# Counter_Display_v1_dynamicLED.net
KiCad netlist of a schematic drawn in Altium Designer
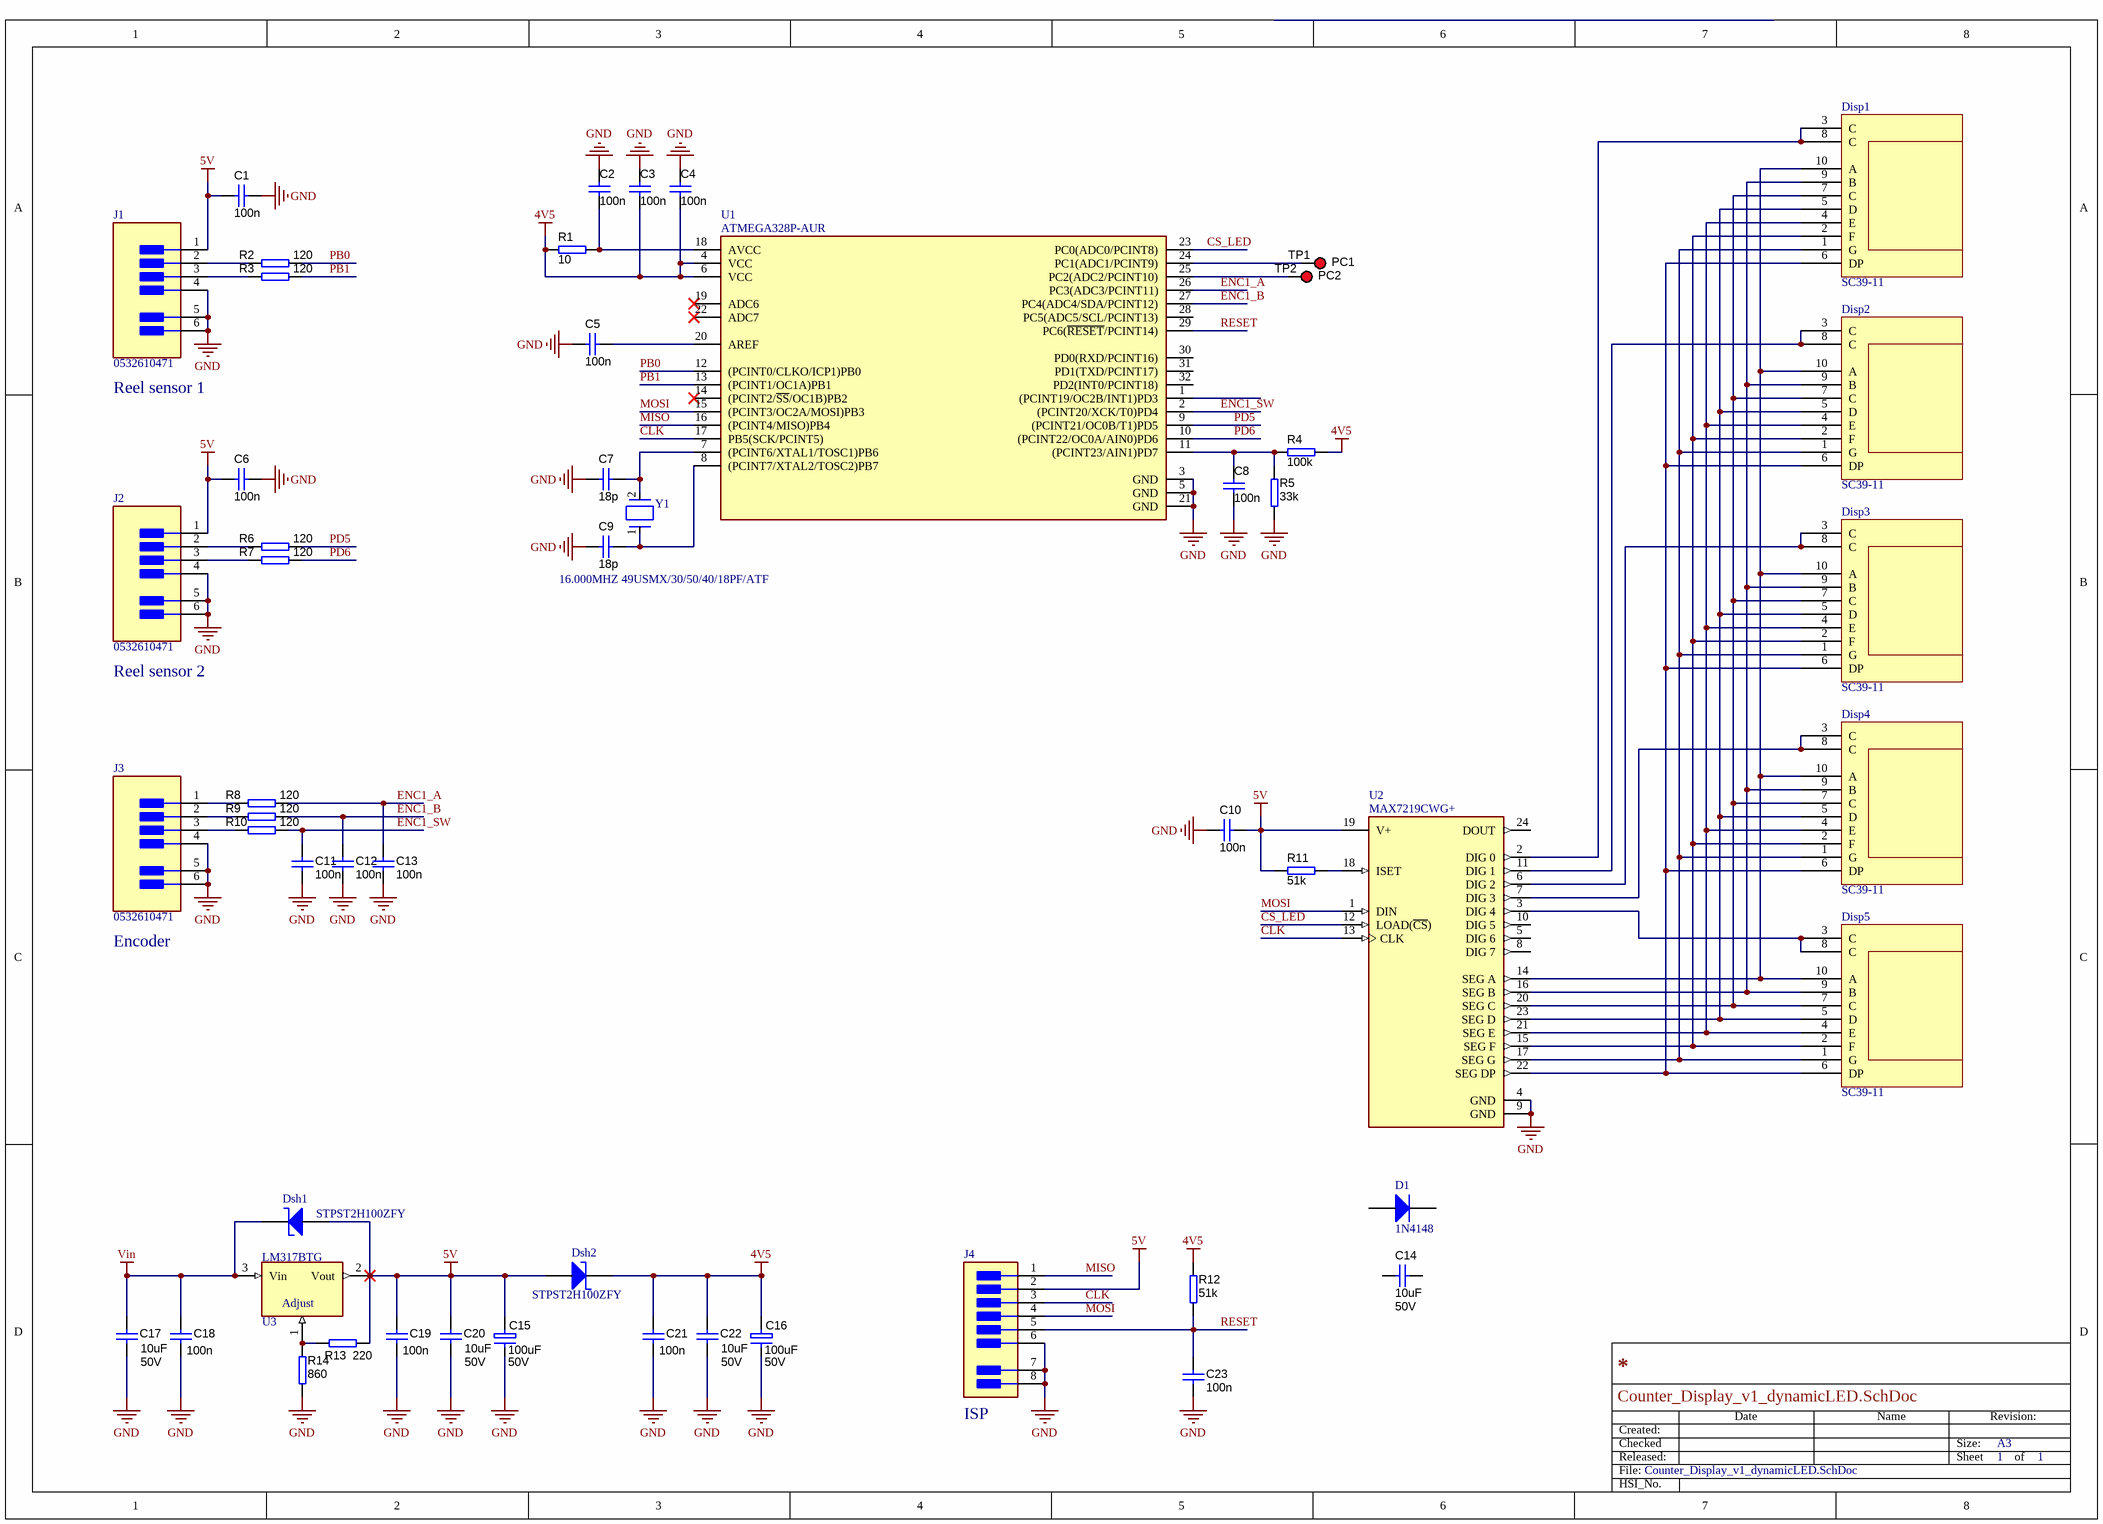
[diagram p0: Counter_Display_v1_dynamicLED.SchDoc]

(export (version "E")
  (design (tool "Eeschema 10.0.6"))
  (components
    (comp (ref "C1")
      (value "100n")
      (footprint "0805_HV")
      (description "CAP, CERM, +/- 10%, X7S,  0805")
      (libsource (lib "Const_Cur_Source") (part "C0805"))
    )
    (comp (ref "C2")
      (value "100n")
      (footprint "0805_HV")
      (description "CAP, CERM, +/- 10%, X7S,  0805")
      (libsource (lib "Const_Cur_Source") (part "C0805"))
    )
    (comp (ref "C3")
      (value "100n")
      (footprint "0805_HV")
      (description "CAP, CERM, +/- 10%, X7S,  0805")
      (libsource (lib "Const_Cur_Source") (part "C0805"))
    )
    (comp (ref "C4")
      (value "100n")
      (footprint "0805_HV")
      (description "CAP, CERM, +/- 10%, X7S,  0805")
      (libsource (lib "Const_Cur_Source") (part "C0805"))
    )
    (comp (ref "C5")
      (value "100n")
      (footprint "0805_HV")
      (description "CAP, CERM, +/- 10%, X7S,  0805")
      (libsource (lib "Const_Cur_Source") (part "C0805"))
    )
    (comp (ref "C6")
      (value "100n")
      (footprint "0805_HV")
      (description "CAP, CERM, +/- 10%, X7S,  0805")
      (libsource (lib "Const_Cur_Source") (part "C0805"))
    )
    (comp (ref "C7")
      (value "18p")
      (footprint "0805_HV")
      (description "CAP, CERM, +/- 10%, X7S,  0805")
      (libsource (lib "Const_Cur_Source") (part "C0805"))
    )
    (comp (ref "C8")
      (value "100n")
      (footprint "0805_HV")
      (description "CAP, CERM, +/- 10%, X7S,  0805")
      (libsource (lib "Const_Cur_Source") (part "C0805"))
    )
    (comp (ref "C9")
      (value "18p")
      (footprint "0805_HV")
      (description "CAP, CERM, +/- 10%, X7S,  0805")
      (libsource (lib "Const_Cur_Source") (part "C0805"))
    )
    (comp (ref "C10")
      (value "100n")
      (footprint "0805_HV")
      (description "CAP, CERM, +/- 10%, X7S,  0805")
      (libsource (lib "Const_Cur_Source") (part "C0805"))
    )
    (comp (ref "C11")
      (value "100n")
      (footprint "0805_HV")
      (description "CAP, CERM, +/- 10%, X7S,  0805")
      (libsource (lib "Const_Cur_Source") (part "C0805"))
    )
    (comp (ref "C12")
      (value "100n")
      (footprint "0805_HV")
      (description "CAP, CERM, +/- 10%, X7S,  0805")
      (libsource (lib "Const_Cur_Source") (part "C0805"))
    )
    (comp (ref "C13")
      (value "100n")
      (footprint "0805_HV")
      (description "CAP, CERM, +/- 10%, X7S,  0805")
      (libsource (lib "Const_Cur_Source") (part "C0805"))
    )
    (comp (ref "C14")
      (value "10uF")
      (footprint "1206_180")
      (description "CAP, CERM, NP0, 1206")
      (fields (field (name "VALUE1") "50V"))
      (libsource (lib "Const_Cur_Source") (part "C1206"))
    )
    (comp (ref "C15")
      (value "100uF")
      (footprint "Elco_Flat_v1")
      (description "CAP, Elco")
      (fields (field (name "VALUE1") "50V"))
      (libsource (lib "Const_Cur_Source") (part "C_Elco"))
    )
    (comp (ref "C16")
      (value "100uF")
      (footprint "Elco_Flat_v1")
      (description "CAP, Elco")
      (fields (field (name "VALUE1") "50V"))
      (libsource (lib "Const_Cur_Source") (part "C_Elco"))
    )
    (comp (ref "C17")
      (value "10uF")
      (footprint "1206_180")
      (description "CAP, CERM, NP0, 1206")
      (fields (field (name "VALUE1") "50V"))
      (libsource (lib "Const_Cur_Source") (part "C1206"))
    )
    (comp (ref "C18")
      (value "100n")
      (footprint "1206")
      (description "CAP, CERM, +/- 10%, X7S,  0805")
      (libsource (lib "Const_Cur_Source") (part "C0805"))
    )
    (comp (ref "C19")
      (value "100n")
      (footprint "0805_HV")
      (description "CAP, CERM, +/- 10%, X7S,  0805")
      (libsource (lib "Const_Cur_Source") (part "C0805"))
    )
    (comp (ref "C20")
      (value "10uF")
      (footprint "1206_180")
      (description "CAP, CERM, NP0, 1206")
      (fields (field (name "VALUE1") "50V"))
      (libsource (lib "Const_Cur_Source") (part "C1206"))
    )
    (comp (ref "C21")
      (value "100n")
      (footprint "0805_HV")
      (description "CAP, CERM, +/- 10%, X7S,  0805")
      (libsource (lib "Const_Cur_Source") (part "C0805"))
    )
    (comp (ref "C22")
      (value "10uF")
      (footprint "1206_180")
      (description "CAP, CERM, NP0, 1206")
      (fields (field (name "VALUE1") "50V"))
      (libsource (lib "Const_Cur_Source") (part "C1206"))
    )
    (comp (ref "C23")
      (value "100n")
      (footprint "0805_HV")
      (description "CAP, CERM, +/- 10%, X7S,  0805")
      (libsource (lib "Const_Cur_Source") (part "C0805"))
    )
    (comp (ref "D1")
      (value "1N4148")
      (footprint "1N4148 (1005)")
      (description "Diode")
      (fields (field (name "Comment") "DIODE_MINI_MELF"))
      (libsource (lib "Const_Cur_Source") (part "DIODE_MINI_MELF"))
    )
    (comp (ref "Disp1")
      (value "SC39-11")
      (footprint "7-Segment-LED  (SC39-11G)")
      (description "SC 39-11 GN")
      (libsource (lib "Const_Cur_Source") (part "SC39-11"))
    )
    (comp (ref "Disp2")
      (value "SC39-11")
      (footprint "7-Segment-LED  (SC39-11G)")
      (description "SC 39-11 GN")
      (libsource (lib "Const_Cur_Source") (part "SC39-11"))
    )
    (comp (ref "Disp3")
      (value "SC39-11")
      (footprint "7-Segment-LED  (SC39-11G)")
      (description "SC 39-11 GN")
      (libsource (lib "Const_Cur_Source") (part "SC39-11"))
    )
    (comp (ref "Disp4")
      (value "SC39-11")
      (footprint "7-Segment-LED  (SC39-11G)")
      (description "SC 39-11 GN")
      (libsource (lib "Const_Cur_Source") (part "SC39-11"))
    )
    (comp (ref "Disp5")
      (value "SC39-11")
      (footprint "7-Segment-LED  (SC39-11G)")
      (description "SC 39-11 GN")
      (libsource (lib "Const_Cur_Source") (part "SC39-11"))
    )
    (comp (ref "Dsh1")
      (value "STPST2H100ZFY")
      (footprint "ONSC-SOD-123-2-425-04_V")
      (description "Diode Shottky")
      (fields (field (name "Comment") "DIODE_Shottky"))
      (libsource (lib "Const_Cur_Source") (part "DIODE_Shottky"))
    )
    (comp (ref "Dsh2")
      (value "STPST2H100ZFY")
      (footprint "ONSC-SOD-123-2-425-04_V")
      (description "Diode Shottky")
      (fields (field (name "Comment") "DIODE_Shottky"))
      (libsource (lib "Const_Cur_Source") (part "DIODE_Shottky"))
    )
    (comp (ref "J1")
      (value "0532610471")
      (footprint "Molex_0532610471_0")
      (libsource (lib "Const_Cur_Source") (part "0532610471"))
    )
    (comp (ref "J2")
      (value "0532610471")
      (footprint "Molex_0532610471_0")
      (libsource (lib "Const_Cur_Source") (part "0532610471"))
    )
    (comp (ref "J3")
      (value "0532610471")
      (footprint "Molex_0532610471_0")
      (libsource (lib "Const_Cur_Source") (part "0532610471"))
    )
    (comp (ref "J4")
      (value "53261-0671")
      (footprint "Molex_53261-0671_0")
      (libsource (lib "Const_Cur_Source") (part "53261-0671"))
    )
    (comp (ref "R1")
      (value "10")
      (footprint "0805_HV")
      (description "RES, 1%, 0.1 W, 0805")
      (libsource (lib "Const_Cur_Source") (part "R0805"))
    )
    (comp (ref "R2")
      (value "120")
      (footprint "0805_HV")
      (description "RES, 1%, 0.1 W, 0805")
      (libsource (lib "Const_Cur_Source") (part "R0805"))
    )
    (comp (ref "R3")
      (value "120")
      (footprint "0805_HV")
      (description "RES, 1%, 0.1 W, 0805")
      (libsource (lib "Const_Cur_Source") (part "R0805"))
    )
    (comp (ref "R4")
      (value "100k")
      (footprint "0805_HV")
      (description "RES, 1%, 0.1 W, 0805")
      (libsource (lib "Const_Cur_Source") (part "R0805"))
    )
    (comp (ref "R5")
      (value "33k")
      (footprint "0805_HV")
      (description "RES, 1%, 0.1 W, 0805")
      (libsource (lib "Const_Cur_Source") (part "R0805"))
    )
    (comp (ref "R6")
      (value "120")
      (footprint "0805_HV")
      (description "RES, 1%, 0.1 W, 0805")
      (libsource (lib "Const_Cur_Source") (part "R0805"))
    )
    (comp (ref "R7")
      (value "120")
      (footprint "0805_HV")
      (description "RES, 1%, 0.1 W, 0805")
      (libsource (lib "Const_Cur_Source") (part "R0805"))
    )
    (comp (ref "R8")
      (value "120")
      (footprint "0805_HV")
      (description "RES, 1%, 0.1 W, 0805")
      (libsource (lib "Const_Cur_Source") (part "R0805"))
    )
    (comp (ref "R9")
      (value "120")
      (footprint "0805_HV")
      (description "RES, 1%, 0.1 W, 0805")
      (libsource (lib "Const_Cur_Source") (part "R0805"))
    )
    (comp (ref "R10")
      (value "120")
      (footprint "0805_HV")
      (description "RES, 1%, 0.1 W, 0805")
      (libsource (lib "Const_Cur_Source") (part "R0805"))
    )
    (comp (ref "R11")
      (value "51k")
      (footprint "0805_HV")
      (description "RES, 1%, 0.1 W, 0805")
      (libsource (lib "Const_Cur_Source") (part "R0805"))
    )
    (comp (ref "R12")
      (value "51k")
      (footprint "0805_HV")
      (description "RES, 1%, 0.1 W, 0805")
      (libsource (lib "Const_Cur_Source") (part "R0805"))
    )
    (comp (ref "R13")
      (value "220")
      (footprint "0805_HV")
      (description "RES, 1%, 0.1 W, 0805")
      (libsource (lib "Const_Cur_Source") (part "R0805"))
    )
    (comp (ref "R14")
      (value "860")
      (footprint "0805_HV")
      (description "RES, 1%, 0.1 W, 0805")
      (libsource (lib "Const_Cur_Source") (part "R0805"))
    )
    (comp (ref "TP1")
      (value "PC1")
      (footprint "TP")
      (description "Test Point, Miniature, Red, TH")
      (fields
        (field (name "PARTNUMBER") "5000")
        (field (name "MANUFACTURER") "Keystone")
        (field (name "PUBLISHER") "Texas Instruments")
      )
      (libsource (lib "Const_Cur_Source") (part "TP"))
    )
    (comp (ref "TP2")
      (value "PC2")
      (footprint "TP")
      (description "Test Point, Miniature, Red, TH")
      (fields
        (field (name "PARTNUMBER") "5000")
        (field (name "MANUFACTURER") "Keystone")
        (field (name "PUBLISHER") "Texas Instruments")
      )
      (libsource (lib "Const_Cur_Source") (part "TP"))
    )
    (comp (ref "U1")
      (value "ATMEGA328P-AU")
      (footprint "ATMEGA328P-AU_0")
      (description "IC AVR AVR® ATmega Microcontroller IC 8-Bit 20MHz 32KB (16K x 16) FLASH 32-TQFP (7x7)")
      (fields
        (field (name "MANUFACTURER") "Atmel")
        (field (name "MOUSER PART NUMBER") "556-ATMEGA328P-AUR")
        (field (name "PART NUMBER") "ATMEGA328P-AUR")
      )
      (libsource (lib "Const_Cur_Source") (part "ATMEGA328P-AU"))
    )
    (comp (ref "U2")
      (value "MAX7219CWG+")
      (footprint "Maxim_Integrated_W24-1_IPC_A")
      (libsource (lib "Const_Cur_Source") (part "MAX7219CWG+"))
    )
    (comp (ref "U3")
      (value "LM317BTG")
      (footprint "ON_Semi_221AB-01_0")
      (libsource (lib "Const_Cur_Source") (part "LM317BTG"))
    )
    (comp (ref "Y1")
      (value "Qartz_16.000MHZ_49USMX-30-50-40-18PF-ATF_eec")
      (footprint "Quartz_16.000MHZ_49USMX-30-50-40-18PF-ATF_0")
      (description "CRYS")
      (fields
        (field (name "MANUFACTURER") "Euroquartz")
        (field (name "OCTOPART PART NUMBER") "45978c55d5b29a50")
        (field (name "PART NUMBER") "16.000MHZ 49USMX/30/50/40/18PF/ATF")
      )
      (libsource (lib "Const_Cur_Source") (part "Qartz_16.000MHZ_49USMX-30-50-40-18PF-ATF_eec"))
    )
  )
  (nets
    (net (code "1") (name "/CLK") (class "Default")
      (node (ref "J4") (pin "3") (pinfunction "3_3") (pintype "passive"))
      (node (ref "U1") (pin "17") (pinfunction "PB5(SCK/PCINT5)_17") (pintype "passive"))
      (node (ref "U2") (pin "13") (pinfunction "CLK_13") (pintype "input"))
    )
    (net (code "2") (name "/CS_LED") (class "Default")
      (node (ref "U1") (pin "23") (pinfunction "PC0(ADC0/PCINT8)_23") (pintype "passive"))
      (node (ref "U2") (pin "12") (pinfunction "LOAD(~{CS})_12") (pintype "input"))
    )
    (net (code "3") (name "/ENC1_A") (class "Default")
      (node (ref "C13") (pin "2") (pinfunction "2_2") (pintype "passive"))
      (node (ref "R8") (pin "2") (pinfunction "2_2") (pintype "passive"))
      (node (ref "U1") (pin "26") (pinfunction "PC3(ADC3/PCINT11)_26") (pintype "passive"))
    )
    (net (code "4") (name "/ENC1_B") (class "Default")
      (node (ref "C12") (pin "2") (pinfunction "2_2") (pintype "passive"))
      (node (ref "R9") (pin "2") (pinfunction "2_2") (pintype "passive"))
      (node (ref "U1") (pin "27") (pinfunction "PC4(ADC4/SDA/PCINT12)_27") (pintype "passive"))
    )
    (net (code "5") (name "/ENC1_SW") (class "Default")
      (node (ref "C11") (pin "2") (pinfunction "2_2") (pintype "passive"))
      (node (ref "R10") (pin "2") (pinfunction "2_2") (pintype "passive"))
      (node (ref "U1") (pin "2") (pinfunction "(PCINT20/XCK/T0)PD4_2") (pintype "passive"))
    )
    (net (code "6") (name "/MISO") (class "Default")
      (node (ref "J4") (pin "1") (pinfunction "1_1") (pintype "passive"))
      (node (ref "U1") (pin "16") (pinfunction "(PCINT4/MISO)PB4_16") (pintype "passive"))
    )
    (net (code "7") (name "/MOSI") (class "Default")
      (node (ref "J4") (pin "4") (pinfunction "4_4") (pintype "passive"))
      (node (ref "U1") (pin "15") (pinfunction "(PCINT3/OC2A/MOSI)PB3_15") (pintype "passive"))
      (node (ref "U2") (pin "1") (pinfunction "DIN_1") (pintype "input"))
    )
    (net (code "8") (name "/PB0") (class "Default")
      (node (ref "R2") (pin "2") (pinfunction "2_2") (pintype "passive"))
      (node (ref "U1") (pin "12") (pinfunction "(PCINT0/CLKO/ICP1)PB0_12") (pintype "passive"))
    )
    (net (code "9") (name "/PB1") (class "Default")
      (node (ref "R3") (pin "2") (pinfunction "2_2") (pintype "passive"))
      (node (ref "U1") (pin "13") (pinfunction "(PCINT1/OC1A)PB1_13") (pintype "passive"))
    )
    (net (code "10") (name "/PD5") (class "Default")
      (node (ref "R6") (pin "2") (pinfunction "2_2") (pintype "passive"))
      (node (ref "U1") (pin "9") (pinfunction "(PCINT21/OC0B/T1)PD5_9") (pintype "passive"))
    )
    (net (code "11") (name "/PD6") (class "Default")
      (node (ref "R7") (pin "2") (pinfunction "2_2") (pintype "passive"))
      (node (ref "U1") (pin "10") (pinfunction "(PCINT22/OC0A/AIN0)PD6_10") (pintype "passive"))
    )
    (net (code "12") (name "/RESET") (class "Default")
      (node (ref "C23") (pin "2") (pinfunction "2_2") (pintype "passive"))
      (node (ref "J4") (pin "5") (pinfunction "5_5") (pintype "passive"))
      (node (ref "R12") (pin "1") (pinfunction "1_1") (pintype "passive"))
      (node (ref "U1") (pin "29") (pinfunction "PC6(~{RESET}/PCINT14)_29") (pintype "passive"))
    )
    (net (code "13") (name "4V5") (class "Default")
      (node (ref "C16") (pin "1") (pinfunction "1_1") (pintype "passive"))
      (node (ref "C21") (pin "1") (pinfunction "1_1") (pintype "passive"))
      (node (ref "C22") (pin "1") (pinfunction "1_1") (pintype "passive"))
      (node (ref "C3") (pin "1") (pinfunction "1_1") (pintype "passive"))
      (node (ref "C4") (pin "1") (pinfunction "1_1") (pintype "passive"))
      (node (ref "Dsh2") (pin "K") (pinfunction "K_K") (pintype "passive"))
      (node (ref "R1") (pin "1") (pinfunction "1_1") (pintype "passive"))
      (node (ref "R12") (pin "2") (pinfunction "2_2") (pintype "passive"))
      (node (ref "R4") (pin "2") (pinfunction "2_2") (pintype "passive"))
      (node (ref "U1") (pin "4") (pinfunction "VCC_4") (pintype "passive"))
      (node (ref "U1") (pin "6") (pinfunction "VCC_6") (pintype "passive"))
    )
    (net (code "14") (name "5V") (class "Default")
      (node (ref "C1") (pin "1") (pinfunction "1_1") (pintype "passive"))
      (node (ref "C10") (pin "2") (pinfunction "2_2") (pintype "passive"))
      (node (ref "C15") (pin "1") (pinfunction "1_1") (pintype "passive"))
      (node (ref "C19") (pin "1") (pinfunction "1_1") (pintype "passive"))
      (node (ref "C20") (pin "1") (pinfunction "1_1") (pintype "passive"))
      (node (ref "C6") (pin "1") (pinfunction "1_1") (pintype "passive"))
      (node (ref "Dsh1") (pin "A") (pinfunction "A_A") (pintype "passive"))
      (node (ref "Dsh2") (pin "A") (pinfunction "A_A") (pintype "passive"))
      (node (ref "J1") (pin "1") (pinfunction "1_1") (pintype "passive"))
      (node (ref "J2") (pin "1") (pinfunction "1_1") (pintype "passive"))
      (node (ref "J4") (pin "2") (pinfunction "2_2") (pintype "passive"))
      (node (ref "R11") (pin "1") (pinfunction "1_1") (pintype "passive"))
      (node (ref "R13") (pin "1") (pinfunction "1_1") (pintype "passive"))
      (node (ref "U2") (pin "19") (pinfunction "V+_19") (pintype "power_in"))
      (node (ref "U3") (pin "2") (pinfunction "Vout_2") (pintype "output"))
    )
    (net (code "15") (name "GND") (class "Default")
      (node (ref "C1") (pin "2") (pinfunction "2_2") (pintype "passive"))
      (node (ref "C10") (pin "1") (pinfunction "1_1") (pintype "passive"))
      (node (ref "C11") (pin "1") (pinfunction "1_1") (pintype "passive"))
      (node (ref "C12") (pin "1") (pinfunction "1_1") (pintype "passive"))
      (node (ref "C13") (pin "1") (pinfunction "1_1") (pintype "passive"))
      (node (ref "C15") (pin "2") (pinfunction "2_2") (pintype "passive"))
      (node (ref "C16") (pin "2") (pinfunction "2_2") (pintype "passive"))
      (node (ref "C17") (pin "2") (pinfunction "2_2") (pintype "passive"))
      (node (ref "C18") (pin "2") (pinfunction "2_2") (pintype "passive"))
      (node (ref "C19") (pin "2") (pinfunction "2_2") (pintype "passive"))
      (node (ref "C2") (pin "2") (pinfunction "2_2") (pintype "passive"))
      (node (ref "C20") (pin "2") (pinfunction "2_2") (pintype "passive"))
      (node (ref "C21") (pin "2") (pinfunction "2_2") (pintype "passive"))
      (node (ref "C22") (pin "2") (pinfunction "2_2") (pintype "passive"))
      (node (ref "C23") (pin "1") (pinfunction "1_1") (pintype "passive"))
      (node (ref "C3") (pin "2") (pinfunction "2_2") (pintype "passive"))
      (node (ref "C4") (pin "2") (pinfunction "2_2") (pintype "passive"))
      (node (ref "C5") (pin "2") (pinfunction "2_2") (pintype "passive"))
      (node (ref "C6") (pin "2") (pinfunction "2_2") (pintype "passive"))
      (node (ref "C7") (pin "2") (pinfunction "2_2") (pintype "passive"))
      (node (ref "C8") (pin "1") (pinfunction "1_1") (pintype "passive"))
      (node (ref "C9") (pin "2") (pinfunction "2_2") (pintype "passive"))
      (node (ref "J1") (pin "4") (pinfunction "4_4") (pintype "passive"))
      (node (ref "J1") (pin "5") (pinfunction "MNT_1_5") (pintype "passive"))
      (node (ref "J1") (pin "6") (pinfunction "MNT_2_6") (pintype "passive"))
      (node (ref "J2") (pin "4") (pinfunction "4_4") (pintype "passive"))
      (node (ref "J2") (pin "5") (pinfunction "MNT_1_5") (pintype "passive"))
      (node (ref "J2") (pin "6") (pinfunction "MNT_2_6") (pintype "passive"))
      (node (ref "J3") (pin "4") (pinfunction "4_4") (pintype "passive"))
      (node (ref "J3") (pin "5") (pinfunction "MNT_1_5") (pintype "passive"))
      (node (ref "J3") (pin "6") (pinfunction "MNT_2_6") (pintype "passive"))
      (node (ref "J4") (pin "6") (pinfunction "6_6") (pintype "passive"))
      (node (ref "J4") (pin "7") (pinfunction "MNT_1_7") (pintype "passive"))
      (node (ref "J4") (pin "8") (pinfunction "MNT_2_8") (pintype "passive"))
      (node (ref "R14") (pin "2") (pinfunction "2_2") (pintype "passive"))
      (node (ref "R5") (pin "1") (pinfunction "1_1") (pintype "passive"))
      (node (ref "U1") (pin "21") (pinfunction "GND_21") (pintype "passive"))
      (node (ref "U1") (pin "3") (pinfunction "GND_3") (pintype "passive"))
      (node (ref "U1") (pin "5") (pinfunction "GND_5") (pintype "passive"))
      (node (ref "U2") (pin "4") (pinfunction "GND_4") (pintype "power_in"))
      (node (ref "U2") (pin "9") (pinfunction "GND_9") (pintype "power_in"))
    )
    (net (code "16") (name "Net-(Disp1-A)") (class "Default")
      (node (ref "Disp1") (pin "10") (pinfunction "A_10") (pintype "passive"))
      (node (ref "Disp2") (pin "10") (pinfunction "A_10") (pintype "passive"))
      (node (ref "Disp3") (pin "10") (pinfunction "A_10") (pintype "passive"))
      (node (ref "Disp4") (pin "10") (pinfunction "A_10") (pintype "passive"))
      (node (ref "Disp5") (pin "10") (pinfunction "A_10") (pintype "passive"))
      (node (ref "U2") (pin "14") (pinfunction "SEG_A_14") (pintype "output"))
    )
    (net (code "17") (name "Net-(Disp1-B)") (class "Default")
      (node (ref "Disp1") (pin "9") (pinfunction "B_9") (pintype "passive"))
      (node (ref "Disp2") (pin "9") (pinfunction "B_9") (pintype "passive"))
      (node (ref "Disp3") (pin "9") (pinfunction "B_9") (pintype "passive"))
      (node (ref "Disp4") (pin "9") (pinfunction "B_9") (pintype "passive"))
      (node (ref "Disp5") (pin "9") (pinfunction "B_9") (pintype "passive"))
      (node (ref "U2") (pin "16") (pinfunction "SEG_B_16") (pintype "output"))
    )
    (net (code "18") (name "Net-(Disp1-D)") (class "Default")
      (node (ref "Disp1") (pin "5") (pinfunction "D_5") (pintype "passive"))
      (node (ref "Disp2") (pin "5") (pinfunction "D_5") (pintype "passive"))
      (node (ref "Disp3") (pin "5") (pinfunction "D_5") (pintype "passive"))
      (node (ref "Disp4") (pin "5") (pinfunction "D_5") (pintype "passive"))
      (node (ref "Disp5") (pin "5") (pinfunction "D_5") (pintype "passive"))
      (node (ref "U2") (pin "23") (pinfunction "SEG_D_23") (pintype "output"))
    )
    (net (code "19") (name "Net-(Disp1-DP)") (class "Default")
      (node (ref "Disp1") (pin "6") (pinfunction "DP_6") (pintype "passive"))
      (node (ref "Disp2") (pin "6") (pinfunction "DP_6") (pintype "passive"))
      (node (ref "Disp3") (pin "6") (pinfunction "DP_6") (pintype "passive"))
      (node (ref "Disp4") (pin "6") (pinfunction "DP_6") (pintype "passive"))
      (node (ref "Disp5") (pin "6") (pinfunction "DP_6") (pintype "passive"))
      (node (ref "U2") (pin "22") (pinfunction "SEG_DP_22") (pintype "output"))
    )
    (net (code "20") (name "Net-(Disp1-E)") (class "Default")
      (node (ref "Disp1") (pin "4") (pinfunction "E_4") (pintype "passive"))
      (node (ref "Disp2") (pin "4") (pinfunction "E_4") (pintype "passive"))
      (node (ref "Disp3") (pin "4") (pinfunction "E_4") (pintype "passive"))
      (node (ref "Disp4") (pin "4") (pinfunction "E_4") (pintype "passive"))
      (node (ref "Disp5") (pin "4") (pinfunction "E_4") (pintype "passive"))
      (node (ref "U2") (pin "21") (pinfunction "SEG_E_21") (pintype "output"))
    )
    (net (code "21") (name "Net-(Disp1-F)") (class "Default")
      (node (ref "Disp1") (pin "2") (pinfunction "F_2") (pintype "passive"))
      (node (ref "Disp2") (pin "2") (pinfunction "F_2") (pintype "passive"))
      (node (ref "Disp3") (pin "2") (pinfunction "F_2") (pintype "passive"))
      (node (ref "Disp4") (pin "2") (pinfunction "F_2") (pintype "passive"))
      (node (ref "Disp5") (pin "2") (pinfunction "F_2") (pintype "passive"))
      (node (ref "U2") (pin "15") (pinfunction "SEG_F_15") (pintype "output"))
    )
    (net (code "22") (name "Net-(Disp1-G)") (class "Default")
      (node (ref "Disp1") (pin "1") (pinfunction "G_1") (pintype "passive"))
      (node (ref "Disp2") (pin "1") (pinfunction "G_1") (pintype "passive"))
      (node (ref "Disp3") (pin "1") (pinfunction "G_1") (pintype "passive"))
      (node (ref "Disp4") (pin "1") (pinfunction "G_1") (pintype "passive"))
      (node (ref "Disp5") (pin "1") (pinfunction "G_1") (pintype "passive"))
      (node (ref "U2") (pin "17") (pinfunction "SEG_G_17") (pintype "output"))
    )
    (net (code "23") (name "Net-(J1-Pad2)") (class "Default")
      (node (ref "J1") (pin "2") (pinfunction "2_2") (pintype "passive"))
      (node (ref "R2") (pin "1") (pinfunction "1_1") (pintype "passive"))
    )
    (net (code "24") (name "Net-(J1-Pad3)") (class "Default")
      (node (ref "J1") (pin "3") (pinfunction "3_3") (pintype "passive"))
      (node (ref "R3") (pin "1") (pinfunction "1_1") (pintype "passive"))
    )
    (net (code "25") (name "Net-(J2-Pad2)") (class "Default")
      (node (ref "J2") (pin "2") (pinfunction "2_2") (pintype "passive"))
      (node (ref "R6") (pin "1") (pinfunction "1_1") (pintype "passive"))
    )
    (net (code "26") (name "Net-(J2-Pad3)") (class "Default")
      (node (ref "J2") (pin "3") (pinfunction "3_3") (pintype "passive"))
      (node (ref "R7") (pin "1") (pinfunction "1_1") (pintype "passive"))
    )
    (net (code "27") (name "Net-(J3-Pad1)") (class "Default")
      (node (ref "J3") (pin "1") (pinfunction "1_1") (pintype "passive"))
      (node (ref "R8") (pin "1") (pinfunction "1_1") (pintype "passive"))
    )
    (net (code "28") (name "Net-(J3-Pad2)") (class "Default")
      (node (ref "J3") (pin "2") (pinfunction "2_2") (pintype "passive"))
      (node (ref "R9") (pin "1") (pinfunction "1_1") (pintype "passive"))
    )
    (net (code "29") (name "Net-(J3-Pad3)") (class "Default")
      (node (ref "J3") (pin "3") (pinfunction "3_3") (pintype "passive"))
      (node (ref "R10") (pin "1") (pinfunction "1_1") (pintype "passive"))
    )
    (net (code "30") (name "Net-(U1-(PCINT6{slash}XTAL1{slash}TOSC1)PB6)") (class "Default")
      (node (ref "C7") (pin "1") (pinfunction "1_1") (pintype "passive"))
      (node (ref "U1") (pin "7") (pinfunction "(PCINT6/XTAL1/TOSC1)PB6_7") (pintype "passive"))
      (node (ref "Y1") (pin "2") (pinfunction "2_2") (pintype "passive"))
    )
    (net (code "31") (name "Net-(U1-(PCINT7{slash}XTAL2{slash}TOSC2)PB7)") (class "Default")
      (node (ref "C9") (pin "1") (pinfunction "1_1") (pintype "passive"))
      (node (ref "U1") (pin "8") (pinfunction "(PCINT7/XTAL2/TOSC2)PB7_8") (pintype "passive"))
      (node (ref "Y1") (pin "1") (pinfunction "1_1") (pintype "passive"))
    )
    (net (code "32") (name "Net-(U1-(PCINT23{slash}AIN1)PD7)") (class "Default")
      (node (ref "C8") (pin "2") (pinfunction "2_2") (pintype "passive"))
      (node (ref "R4") (pin "1") (pinfunction "1_1") (pintype "passive"))
      (node (ref "R5") (pin "2") (pinfunction "2_2") (pintype "passive"))
      (node (ref "U1") (pin "11") (pinfunction "(PCINT23/AIN1)PD7_11") (pintype "passive"))
    )
    (net (code "33") (name "Net-(U1-AREF)") (class "Default")
      (node (ref "C5") (pin "1") (pinfunction "1_1") (pintype "passive"))
      (node (ref "U1") (pin "20") (pinfunction "AREF_20") (pintype "passive"))
    )
    (net (code "34") (name "Net-(U1-AVCC)") (class "Default")
      (node (ref "C2") (pin "1") (pinfunction "1_1") (pintype "passive"))
      (node (ref "R1") (pin "2") (pinfunction "2_2") (pintype "passive"))
      (node (ref "U1") (pin "18") (pinfunction "AVCC_18") (pintype "passive"))
    )
    (net (code "35") (name "Net-(U1-PC1(ADC1{slash}PCINT9))") (class "Default")
      (node (ref "TP1") (pin "1") (pintype "passive"))
      (node (ref "U1") (pin "24") (pinfunction "PC1(ADC1/PCINT9)_24") (pintype "passive"))
    )
    (net (code "36") (name "Net-(U1-PC2(ADC2{slash}PCINT10))") (class "Default")
      (node (ref "TP2") (pin "1") (pintype "passive"))
      (node (ref "U1") (pin "25") (pinfunction "PC2(ADC2/PCINT10)_25") (pintype "passive"))
    )
    (net (code "37") (name "Net-(U2-DIG_0)") (class "Default")
      (node (ref "Disp1") (pin "3") (pinfunction "C_3") (pintype "passive"))
      (node (ref "Disp1") (pin "8") (pinfunction "C_8") (pintype "passive"))
      (node (ref "U2") (pin "2") (pinfunction "DIG_0_2") (pintype "output"))
    )
    (net (code "38") (name "Net-(U2-DIG_1)") (class "Default")
      (node (ref "Disp2") (pin "3") (pinfunction "C_3") (pintype "passive"))
      (node (ref "Disp2") (pin "8") (pinfunction "C_8") (pintype "passive"))
      (node (ref "U2") (pin "11") (pinfunction "DIG_1_11") (pintype "output"))
    )
    (net (code "39") (name "Net-(U2-DIG_2)") (class "Default")
      (node (ref "Disp3") (pin "3") (pinfunction "C_3") (pintype "passive"))
      (node (ref "Disp3") (pin "8") (pinfunction "C_8") (pintype "passive"))
      (node (ref "U2") (pin "6") (pinfunction "DIG_2_6") (pintype "output"))
    )
    (net (code "40") (name "Net-(U2-DIG_3)") (class "Default")
      (node (ref "Disp4") (pin "3") (pinfunction "C_3") (pintype "passive"))
      (node (ref "Disp4") (pin "8") (pinfunction "C_8") (pintype "passive"))
      (node (ref "U2") (pin "7") (pinfunction "DIG_3_7") (pintype "output"))
    )
    (net (code "41") (name "Net-(U2-DIG_4)") (class "Default")
      (node (ref "Disp5") (pin "3") (pinfunction "C_3") (pintype "passive"))
      (node (ref "Disp5") (pin "8") (pinfunction "C_8") (pintype "passive"))
      (node (ref "U2") (pin "3") (pinfunction "DIG_4_3") (pintype "output"))
    )
    (net (code "42") (name "Net-(U2-ISET)") (class "Default")
      (node (ref "R11") (pin "2") (pinfunction "2_2") (pintype "passive"))
      (node (ref "U2") (pin "18") (pinfunction "ISET_18") (pintype "input"))
    )
    (net (code "43") (name "Net-(U2-SEG_C)") (class "Default")
      (node (ref "Disp1") (pin "7") (pinfunction "C_7") (pintype "passive"))
      (node (ref "Disp2") (pin "7") (pinfunction "C_7") (pintype "passive"))
      (node (ref "Disp3") (pin "7") (pinfunction "C_7") (pintype "passive"))
      (node (ref "Disp4") (pin "7") (pinfunction "C_7") (pintype "passive"))
      (node (ref "Disp5") (pin "7") (pinfunction "C_7") (pintype "passive"))
      (node (ref "U2") (pin "20") (pinfunction "SEG_C_20") (pintype "output"))
    )
    (net (code "44") (name "Net-(U3-Adjust)") (class "Default")
      (node (ref "R13") (pin "2") (pinfunction "2_2") (pintype "passive"))
      (node (ref "R14") (pin "1") (pinfunction "1_1") (pintype "passive"))
      (node (ref "U3") (pin "1") (pinfunction "Adjust_1") (pintype "input"))
    )
    (net (code "45") (name "Vin") (class "Default")
      (node (ref "C17") (pin "1") (pinfunction "1_1") (pintype "passive"))
      (node (ref "C18") (pin "1") (pinfunction "1_1") (pintype "passive"))
      (node (ref "Dsh1") (pin "K") (pinfunction "K_K") (pintype "passive"))
      (node (ref "U3") (pin "3") (pinfunction "Vin_3") (pintype "input"))
    )
    (net (code "46") (name "unconnected-(C14-Pad1)") (class "Default")
      (node (ref "C14") (pin "1") (pinfunction "1_1") (pintype "passive"))
    )
    (net (code "47") (name "unconnected-(C14-Pad2)") (class "Default")
      (node (ref "C14") (pin "2") (pinfunction "2_2") (pintype "passive"))
    )
    (net (code "48") (name "unconnected-(D1-PadA)") (class "Default")
      (node (ref "D1") (pin "A") (pinfunction "A_A") (pintype "passive"))
    )
    (net (code "49") (name "unconnected-(D1-PadK)") (class "Default")
      (node (ref "D1") (pin "K") (pinfunction "K_K") (pintype "passive"))
    )
    (net (code "50") (name "unconnected-(U1-(PCINT2{slash}~{SS}{slash}OC1B)PB2-Pad14)") (class "Default")
      (node (ref "U1") (pin "14") (pinfunction "(PCINT2/~{SS}/OC1B)PB2_14") (pintype "passive+no_connect"))
    )
    (net (code "51") (name "unconnected-(U1-(PCINT19{slash}OC2B{slash}INT1)PD3-Pad1)") (class "Default")
      (node (ref "U1") (pin "1") (pinfunction "(PCINT19/OC2B/INT1)PD3_1") (pintype "passive"))
    )
    (net (code "52") (name "unconnected-(U1-ADC6-Pad19)") (class "Default")
      (node (ref "U1") (pin "19") (pinfunction "ADC6_19") (pintype "passive+no_connect"))
    )
    (net (code "53") (name "unconnected-(U1-ADC7-Pad22)") (class "Default")
      (node (ref "U1") (pin "22") (pinfunction "ADC7_22") (pintype "passive+no_connect"))
    )
    (net (code "54") (name "unconnected-(U1-PC5(ADC5{slash}SCL{slash}PCINT13)-Pad28)") (class "Default")
      (node (ref "U1") (pin "28") (pinfunction "PC5(ADC5/SCL/PCINT13)_28") (pintype "passive"))
    )
    (net (code "55") (name "unconnected-(U1-PD0(RXD{slash}PCINT16)-Pad30)") (class "Default")
      (node (ref "U1") (pin "30") (pinfunction "PD0(RXD/PCINT16)_30") (pintype "passive"))
    )
    (net (code "56") (name "unconnected-(U1-PD1(TXD{slash}PCINT17)-Pad31)") (class "Default")
      (node (ref "U1") (pin "31") (pinfunction "PD1(TXD/PCINT17)_31") (pintype "passive"))
    )
    (net (code "57") (name "unconnected-(U1-PD2(INT0{slash}PCINT18)-Pad32)") (class "Default")
      (node (ref "U1") (pin "32") (pinfunction "PD2(INT0/PCINT18)_32") (pintype "passive"))
    )
    (net (code "58") (name "unconnected-(U2-DIG_5-Pad10)") (class "Default")
      (node (ref "U2") (pin "10") (pinfunction "DIG_5_10") (pintype "output"))
    )
    (net (code "59") (name "unconnected-(U2-DIG_6-Pad5)") (class "Default")
      (node (ref "U2") (pin "5") (pinfunction "DIG_6_5") (pintype "output"))
    )
    (net (code "60") (name "unconnected-(U2-DIG_7-Pad8)") (class "Default")
      (node (ref "U2") (pin "8") (pinfunction "DIG_7_8") (pintype "output"))
    )
    (net (code "61") (name "unconnected-(U2-DOUT-Pad24)") (class "Default")
      (node (ref "U2") (pin "24") (pinfunction "DOUT_24") (pintype "output"))
    )
  )
)
